# DR_EIB-128_MillMax.net
KiCad netlist of a schematic drawn in EAGLE
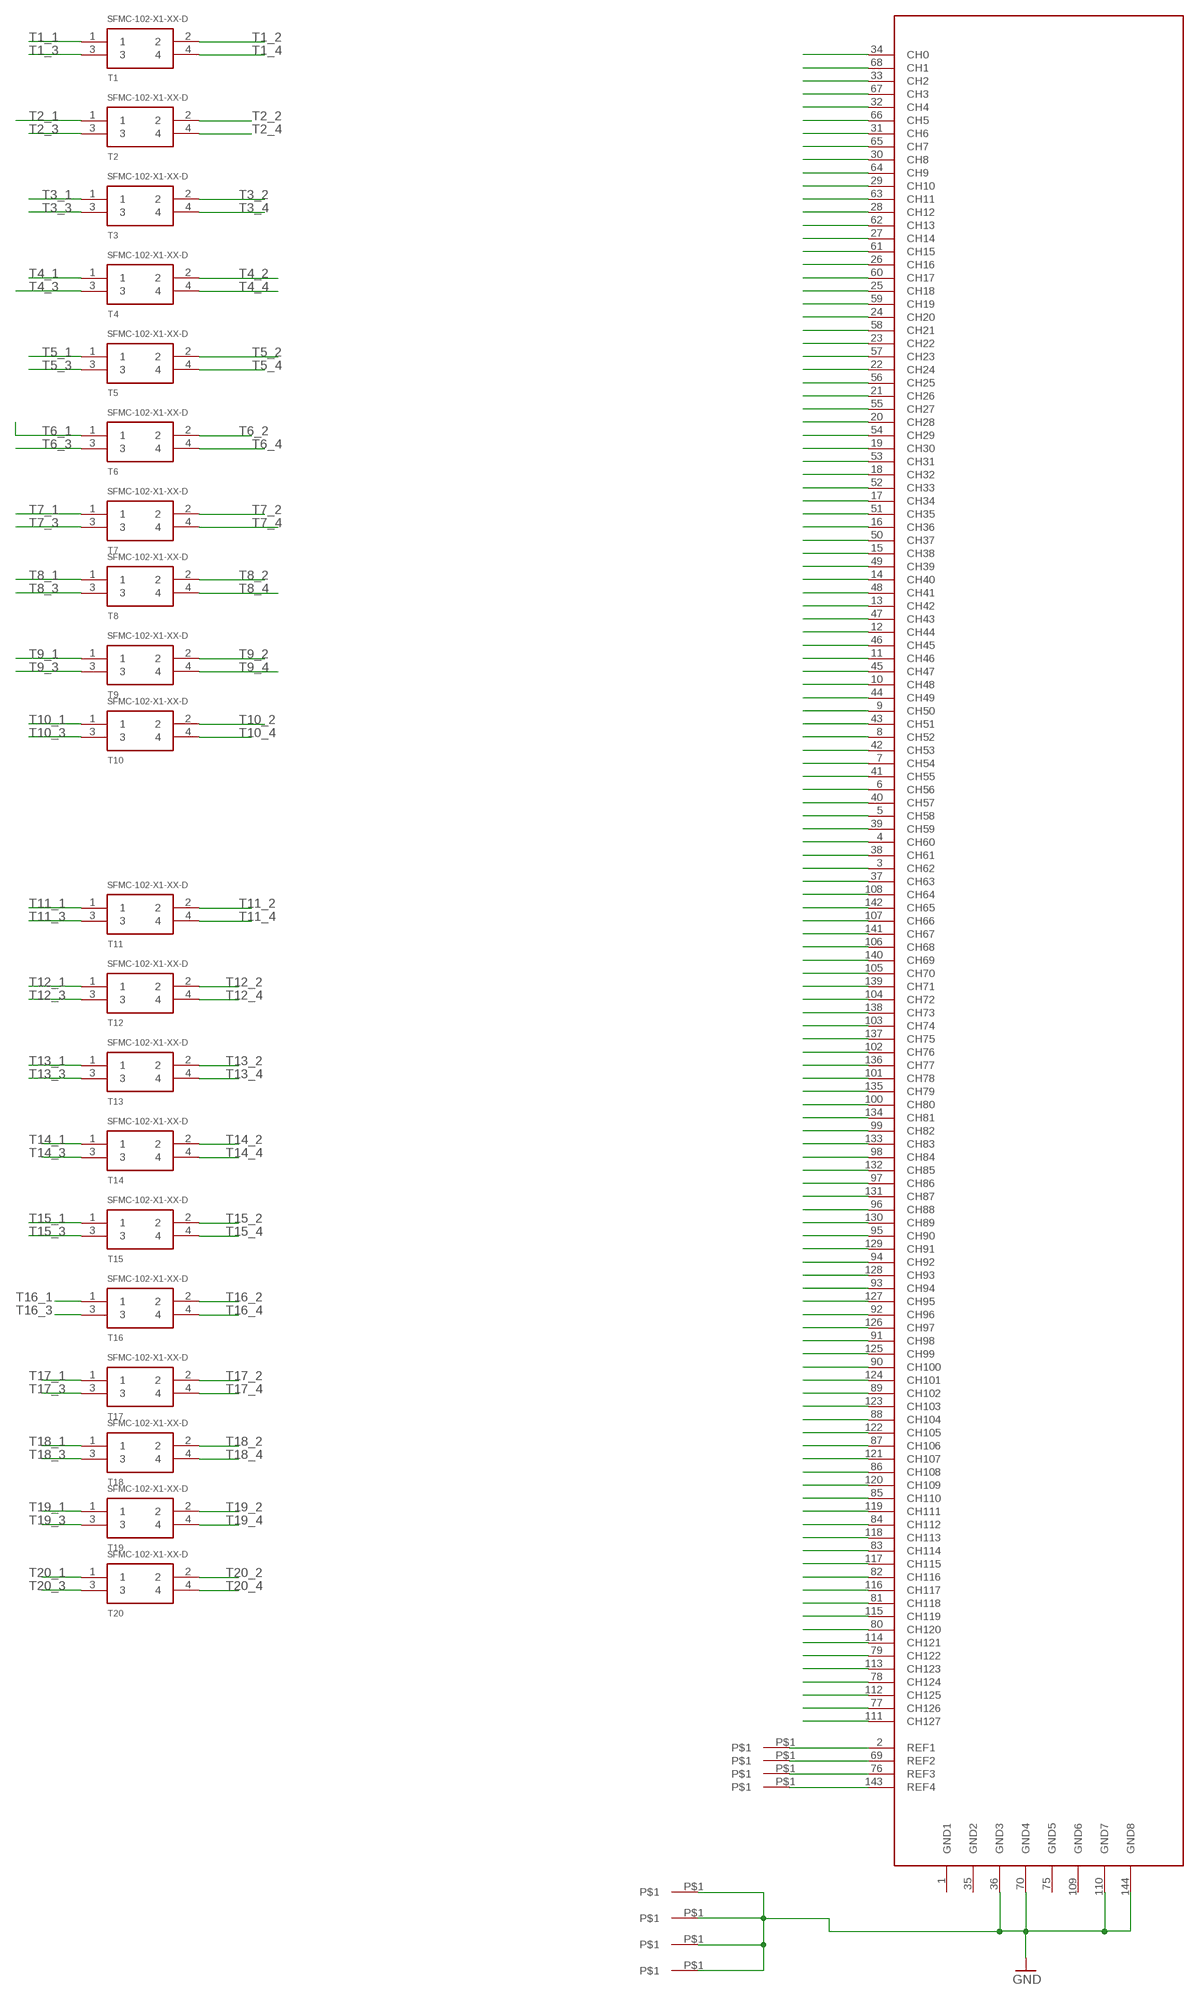
[diagram p0: schematic, sheet 1]

(export (version "E")
  (design (tool "Eeschema 10.0.6"))
  (components
    (comp (ref "T1")
      (value "SFMC-102-X1-XX-D")
      (footprint "eagle-import:SFMC-102-X1-XX-D")
      (libsource (lib "eagle-import") (part "SFMC-102-X1-XX-D"))
    )
    (comp (ref "T2")
      (value "SFMC-102-X1-XX-D")
      (footprint "eagle-import:SFMC-102-X1-XX-D")
      (libsource (lib "eagle-import") (part "SFMC-102-X1-XX-D"))
    )
    (comp (ref "T3")
      (value "SFMC-102-X1-XX-D")
      (footprint "eagle-import:SFMC-102-X1-XX-D")
      (libsource (lib "eagle-import") (part "SFMC-102-X1-XX-D"))
    )
    (comp (ref "T4")
      (value "SFMC-102-X1-XX-D")
      (footprint "eagle-import:SFMC-102-X1-XX-D")
      (libsource (lib "eagle-import") (part "SFMC-102-X1-XX-D"))
    )
    (comp (ref "T5")
      (value "SFMC-102-X1-XX-D")
      (footprint "eagle-import:SFMC-102-X1-XX-D")
      (libsource (lib "eagle-import") (part "SFMC-102-X1-XX-D"))
    )
    (comp (ref "T6")
      (value "SFMC-102-X1-XX-D")
      (footprint "eagle-import:SFMC-102-X1-XX-D")
      (libsource (lib "eagle-import") (part "SFMC-102-X1-XX-D"))
    )
    (comp (ref "T7")
      (value "SFMC-102-X1-XX-D")
      (footprint "eagle-import:SFMC-102-X1-XX-D")
      (libsource (lib "eagle-import") (part "SFMC-102-X1-XX-D"))
    )
    (comp (ref "T8")
      (value "SFMC-102-X1-XX-D")
      (footprint "eagle-import:SFMC-102-X1-XX-D")
      (libsource (lib "eagle-import") (part "SFMC-102-X1-XX-D"))
    )
    (comp (ref "T9")
      (value "SFMC-102-X1-XX-D")
      (footprint "eagle-import:SFMC-102-X1-XX-D")
      (libsource (lib "eagle-import") (part "SFMC-102-X1-XX-D"))
    )
    (comp (ref "T10")
      (value "SFMC-102-X1-XX-D")
      (footprint "eagle-import:SFMC-102-X1-XX-D")
      (libsource (lib "eagle-import") (part "SFMC-102-X1-XX-D"))
    )
    (comp (ref "T11")
      (value "SFMC-102-X1-XX-D")
      (footprint "eagle-import:SFMC-102-X1-XX-D")
      (libsource (lib "eagle-import") (part "SFMC-102-X1-XX-D"))
    )
    (comp (ref "T12")
      (value "SFMC-102-X1-XX-D")
      (footprint "eagle-import:SFMC-102-X1-XX-D")
      (libsource (lib "eagle-import") (part "SFMC-102-X1-XX-D"))
    )
    (comp (ref "T13")
      (value "SFMC-102-X1-XX-D")
      (footprint "eagle-import:SFMC-102-X1-XX-D")
      (libsource (lib "eagle-import") (part "SFMC-102-X1-XX-D"))
    )
    (comp (ref "T14")
      (value "SFMC-102-X1-XX-D")
      (footprint "eagle-import:SFMC-102-X1-XX-D")
      (libsource (lib "eagle-import") (part "SFMC-102-X1-XX-D"))
    )
    (comp (ref "T15")
      (value "SFMC-102-X1-XX-D")
      (footprint "eagle-import:SFMC-102-X1-XX-D")
      (libsource (lib "eagle-import") (part "SFMC-102-X1-XX-D"))
    )
    (comp (ref "T16")
      (value "SFMC-102-X1-XX-D")
      (footprint "eagle-import:SFMC-102-X1-XX-D")
      (libsource (lib "eagle-import") (part "SFMC-102-X1-XX-D"))
    )
    (comp (ref "T17")
      (value "SFMC-102-X1-XX-D")
      (footprint "eagle-import:SFMC-102-X1-XX-D")
      (libsource (lib "eagle-import") (part "SFMC-102-X1-XX-D"))
    )
    (comp (ref "T18")
      (value "SFMC-102-X1-XX-D")
      (footprint "eagle-import:SFMC-102-X1-XX-D")
      (libsource (lib "eagle-import") (part "SFMC-102-X1-XX-D"))
    )
    (comp (ref "T19")
      (value "SFMC-102-X1-XX-D")
      (footprint "eagle-import:SFMC-102-X1-XX-D")
      (libsource (lib "eagle-import") (part "SFMC-102-X1-XX-D"))
    )
    (comp (ref "T20")
      (value "SFMC-102-X1-XX-D")
      (footprint "eagle-import:SFMC-102-X1-XX-D")
      (libsource (lib "eagle-import") (part "SFMC-102-X1-XX-D"))
    )
    (comp (ref "U$1")
      (value "TARRAYSHUTTLEHOLE")
      (footprint "eagle-import:TARRAYSHUTTLEHOLE")
      (libsource (lib "eagle-import") (part "TARRAYSHUTTLEHOLE"))
    )
    (comp (ref "U$2")
      (value "TARRAYSHUTTLEHOLE")
      (footprint "eagle-import:TARRAYSHUTTLEHOLE")
      (libsource (lib "eagle-import") (part "TARRAYSHUTTLEHOLE"))
    )
    (comp (ref "U$3")
      (value "128CH-MODULE")
      (footprint "eagle-import:128CH-MODULE")
      (libsource (lib "eagle-import") (part "128CH-MODULE"))
    )
    (comp (ref "U$4")
      (value "TARRAYSHUTTLEHOLE")
      (footprint "eagle-import:TARRAYSHUTTLEHOLE")
      (libsource (lib "eagle-import") (part "TARRAYSHUTTLEHOLE"))
    )
    (comp (ref "U$5")
      (value "TARRAYSHUTTLEHOLE")
      (footprint "eagle-import:TARRAYSHUTTLEHOLE")
      (libsource (lib "eagle-import") (part "TARRAYSHUTTLEHOLE"))
    )
    (comp (ref "U$6")
      (value "TARRAYSHUTTLEHOLE")
      (footprint "eagle-import:TARRAYSHUTTLEHOLE")
      (libsource (lib "eagle-import") (part "TARRAYSHUTTLEHOLE"))
    )
    (comp (ref "U$7")
      (value "TARRAYSHUTTLEHOLE")
      (footprint "eagle-import:TARRAYSHUTTLEHOLE")
      (libsource (lib "eagle-import") (part "TARRAYSHUTTLEHOLE"))
    )
    (comp (ref "U$8")
      (value "TARRAYSHUTTLEHOLE")
      (footprint "eagle-import:TARRAYSHUTTLEHOLE")
      (libsource (lib "eagle-import") (part "TARRAYSHUTTLEHOLE"))
    )
    (comp (ref "U$9")
      (value "TARRAYSHUTTLEHOLE")
      (footprint "eagle-import:TARRAYSHUTTLEHOLE")
      (libsource (lib "eagle-import") (part "TARRAYSHUTTLEHOLE"))
    )
  )
  (nets
    (net (code "1") (name "/GND1") (class "Default")
      (node (ref "U$3") (pin "1") (pinfunction "GND1_1") (pintype "power_in"))
    )
    (net (code "2") (name "/GND2") (class "Default")
      (node (ref "U$3") (pin "35") (pinfunction "GND2_35") (pintype "power_in"))
    )
    (net (code "3") (name "/GND5") (class "Default")
      (node (ref "U$3") (pin "75") (pinfunction "GND5_75") (pintype "power_in"))
    )
    (net (code "4") (name "/GND6") (class "Default")
      (node (ref "U$3") (pin "109") (pinfunction "GND6_109") (pintype "power_in"))
    )
    (net (code "5") (name "/T1_1") (class "Default")
      (node (ref "T1") (pin "1") (pinfunction "1_1") (pintype "bidirectional"))
      (node (ref "U$3") (pin "37") (pinfunction "CH63_37") (pintype "input"))
    )
    (net (code "6") (name "/T1_2") (class "Default")
      (node (ref "T1") (pin "2") (pinfunction "2_2") (pintype "bidirectional"))
      (node (ref "U$3") (pin "38") (pinfunction "CH61_38") (pintype "input"))
    )
    (net (code "7") (name "/T1_3") (class "Default")
      (node (ref "T1") (pin "3") (pinfunction "3_3") (pintype "bidirectional"))
      (node (ref "U$3") (pin "39") (pinfunction "CH59_39") (pintype "input"))
    )
    (net (code "8") (name "/T1_4") (class "Default")
      (node (ref "T1") (pin "4") (pinfunction "4_4") (pintype "bidirectional"))
      (node (ref "U$3") (pin "40") (pinfunction "CH57_40") (pintype "input"))
    )
    (net (code "9") (name "/T2_1") (class "Default")
      (node (ref "T2") (pin "1") (pinfunction "1_1") (pintype "bidirectional"))
      (node (ref "U$3") (pin "6") (pinfunction "CH56_6") (pintype "input"))
    )
    (net (code "10") (name "/T2_2") (class "Default")
      (node (ref "T2") (pin "2") (pinfunction "2_2") (pintype "bidirectional"))
      (node (ref "U$3") (pin "5") (pinfunction "CH58_5") (pintype "input"))
    )
    (net (code "11") (name "/T2_3") (class "Default")
      (node (ref "T2") (pin "3") (pinfunction "3_3") (pintype "bidirectional"))
      (node (ref "U$3") (pin "4") (pinfunction "CH60_4") (pintype "input"))
    )
    (net (code "12") (name "/T2_4") (class "Default")
      (node (ref "T2") (pin "4") (pinfunction "4_4") (pintype "bidirectional"))
      (node (ref "U$3") (pin "3") (pinfunction "CH62_3") (pintype "input"))
    )
    (net (code "13") (name "/T3_1") (class "Default")
      (node (ref "T3") (pin "1") (pinfunction "1_1") (pintype "bidirectional"))
      (node (ref "U$3") (pin "7") (pinfunction "CH54_7") (pintype "input"))
    )
    (net (code "14") (name "/T3_2") (class "Default")
      (node (ref "T3") (pin "2") (pinfunction "2_2") (pintype "bidirectional"))
      (node (ref "U$3") (pin "8") (pinfunction "CH52_8") (pintype "input"))
    )
    (net (code "15") (name "/T3_3") (class "Default")
      (node (ref "T3") (pin "3") (pinfunction "3_3") (pintype "bidirectional"))
      (node (ref "U$3") (pin "9") (pinfunction "CH50_9") (pintype "input"))
    )
    (net (code "16") (name "/T3_4") (class "Default")
      (node (ref "T3") (pin "4") (pinfunction "4_4") (pintype "bidirectional"))
      (node (ref "U$3") (pin "10") (pinfunction "CH48_10") (pintype "input"))
    )
    (net (code "17") (name "/T4_1") (class "Default")
      (node (ref "T4") (pin "1") (pinfunction "1_1") (pintype "bidirectional"))
      (node (ref "U$3") (pin "11") (pinfunction "CH46_11") (pintype "input"))
    )
    (net (code "18") (name "/T4_2") (class "Default")
      (node (ref "T4") (pin "2") (pinfunction "2_2") (pintype "bidirectional"))
      (node (ref "U$3") (pin "12") (pinfunction "CH44_12") (pintype "input"))
    )
    (net (code "19") (name "/T4_3") (class "Default")
      (node (ref "T4") (pin "3") (pinfunction "3_3") (pintype "bidirectional"))
      (node (ref "U$3") (pin "13") (pinfunction "CH42_13") (pintype "input"))
    )
    (net (code "20") (name "/T4_4") (class "Default")
      (node (ref "T4") (pin "4") (pinfunction "4_4") (pintype "bidirectional"))
      (node (ref "U$3") (pin "14") (pinfunction "CH40_14") (pintype "input"))
    )
    (net (code "21") (name "/T5_1") (class "Default")
      (node (ref "T5") (pin "1") (pinfunction "1_1") (pintype "bidirectional"))
      (node (ref "U$3") (pin "15") (pinfunction "CH38_15") (pintype "input"))
    )
    (net (code "22") (name "/T5_2") (class "Default")
      (node (ref "T5") (pin "2") (pinfunction "2_2") (pintype "bidirectional"))
      (node (ref "U$3") (pin "16") (pinfunction "CH36_16") (pintype "input"))
    )
    (net (code "23") (name "/T5_3") (class "Default")
      (node (ref "T5") (pin "3") (pinfunction "3_3") (pintype "bidirectional"))
      (node (ref "U$3") (pin "17") (pinfunction "CH34_17") (pintype "input"))
    )
    (net (code "24") (name "/T5_4") (class "Default")
      (node (ref "T5") (pin "4") (pinfunction "4_4") (pintype "bidirectional"))
      (node (ref "U$3") (pin "18") (pinfunction "CH32_18") (pintype "input"))
    )
    (net (code "25") (name "/T6_1") (class "Default")
      (node (ref "T6") (pin "1") (pinfunction "1_1") (pintype "bidirectional"))
      (node (ref "U$3") (pin "93") (pinfunction "CH94_93") (pintype "input"))
    )
    (net (code "26") (name "/T6_2") (class "Default")
      (node (ref "T6") (pin "2") (pinfunction "2_2") (pintype "bidirectional"))
      (node (ref "U$3") (pin "94") (pinfunction "CH92_94") (pintype "input"))
    )
    (net (code "27") (name "/T6_3") (class "Default")
      (node (ref "T6") (pin "3") (pinfunction "3_3") (pintype "bidirectional"))
      (node (ref "U$3") (pin "95") (pinfunction "CH90_95") (pintype "input"))
    )
    (net (code "28") (name "/T6_4") (class "Default")
      (node (ref "T6") (pin "4") (pinfunction "4_4") (pintype "bidirectional"))
      (node (ref "U$3") (pin "96") (pinfunction "CH88_96") (pintype "input"))
    )
    (net (code "29") (name "/T7_1") (class "Default")
      (node (ref "T7") (pin "1") (pinfunction "1_1") (pintype "bidirectional"))
      (node (ref "U$3") (pin "97") (pinfunction "CH86_97") (pintype "input"))
    )
    (net (code "30") (name "/T7_2") (class "Default")
      (node (ref "T7") (pin "2") (pinfunction "2_2") (pintype "bidirectional"))
      (node (ref "U$3") (pin "98") (pinfunction "CH84_98") (pintype "input"))
    )
    (net (code "31") (name "/T7_3") (class "Default")
      (node (ref "T7") (pin "3") (pinfunction "3_3") (pintype "bidirectional"))
      (node (ref "U$3") (pin "99") (pinfunction "CH82_99") (pintype "input"))
    )
    (net (code "32") (name "/T7_4") (class "Default")
      (node (ref "T7") (pin "4") (pinfunction "4_4") (pintype "bidirectional"))
      (node (ref "U$3") (pin "100") (pinfunction "CH80_100") (pintype "input"))
    )
    (net (code "33") (name "/T8_1") (class "Default")
      (node (ref "T8") (pin "1") (pinfunction "1_1") (pintype "bidirectional"))
      (node (ref "U$3") (pin "101") (pinfunction "CH78_101") (pintype "input"))
    )
    (net (code "34") (name "/T8_2") (class "Default")
      (node (ref "T8") (pin "2") (pinfunction "2_2") (pintype "bidirectional"))
      (node (ref "U$3") (pin "102") (pinfunction "CH76_102") (pintype "input"))
    )
    (net (code "35") (name "/T8_3") (class "Default")
      (node (ref "T8") (pin "3") (pinfunction "3_3") (pintype "bidirectional"))
      (node (ref "U$3") (pin "103") (pinfunction "CH74_103") (pintype "input"))
    )
    (net (code "36") (name "/T8_4") (class "Default")
      (node (ref "T8") (pin "4") (pinfunction "4_4") (pintype "bidirectional"))
      (node (ref "U$3") (pin "104") (pinfunction "CH72_104") (pintype "input"))
    )
    (net (code "37") (name "/T9_1") (class "Default")
      (node (ref "T9") (pin "1") (pinfunction "1_1") (pintype "bidirectional"))
      (node (ref "U$3") (pin "108") (pinfunction "CH64_108") (pintype "input"))
    )
    (net (code "38") (name "/T9_2") (class "Default")
      (node (ref "T9") (pin "2") (pinfunction "2_2") (pintype "bidirectional"))
      (node (ref "U$3") (pin "107") (pinfunction "CH66_107") (pintype "input"))
    )
    (net (code "39") (name "/T9_3") (class "Default")
      (node (ref "T9") (pin "3") (pinfunction "3_3") (pintype "bidirectional"))
      (node (ref "U$3") (pin "106") (pinfunction "CH68_106") (pintype "input"))
    )
    (net (code "40") (name "/T9_4") (class "Default")
      (node (ref "T9") (pin "4") (pinfunction "4_4") (pintype "bidirectional"))
      (node (ref "U$3") (pin "105") (pinfunction "CH70_105") (pintype "input"))
    )
    (net (code "41") (name "/T10_1") (class "Default")
      (node (ref "T10") (pin "1") (pinfunction "1_1") (pintype "bidirectional"))
      (node (ref "U$3") (pin "139") (pinfunction "CH71_139") (pintype "input"))
    )
    (net (code "42") (name "/T10_2") (class "Default")
      (node (ref "T10") (pin "2") (pinfunction "2_2") (pintype "bidirectional"))
      (node (ref "U$3") (pin "140") (pinfunction "CH69_140") (pintype "input"))
    )
    (net (code "43") (name "/T10_3") (class "Default")
      (node (ref "T10") (pin "3") (pinfunction "3_3") (pintype "bidirectional"))
      (node (ref "U$3") (pin "141") (pinfunction "CH67_141") (pintype "input"))
    )
    (net (code "44") (name "/T10_4") (class "Default")
      (node (ref "T10") (pin "4") (pinfunction "4_4") (pintype "bidirectional"))
      (node (ref "U$3") (pin "142") (pinfunction "CH65_142") (pintype "input"))
    )
    (net (code "45") (name "/T11_1") (class "Default")
      (node (ref "T11") (pin "1") (pinfunction "1_1") (pintype "bidirectional"))
      (node (ref "U$3") (pin "111") (pinfunction "CH127_111") (pintype "input"))
    )
    (net (code "46") (name "/T11_2") (class "Default")
      (node (ref "T11") (pin "2") (pinfunction "2_2") (pintype "bidirectional"))
      (node (ref "U$3") (pin "112") (pinfunction "CH125_112") (pintype "input"))
    )
    (net (code "47") (name "/T11_3") (class "Default")
      (node (ref "T11") (pin "3") (pinfunction "3_3") (pintype "bidirectional"))
      (node (ref "U$3") (pin "113") (pinfunction "CH123_113") (pintype "input"))
    )
    (net (code "48") (name "/T11_4") (class "Default")
      (node (ref "T11") (pin "4") (pinfunction "4_4") (pintype "bidirectional"))
      (node (ref "U$3") (pin "114") (pinfunction "CH121_114") (pintype "input"))
    )
    (net (code "49") (name "/T12_1") (class "Default")
      (node (ref "T12") (pin "1") (pinfunction "1_1") (pintype "bidirectional"))
      (node (ref "U$3") (pin "80") (pinfunction "CH120_80") (pintype "input"))
    )
    (net (code "50") (name "/T12_2") (class "Default")
      (node (ref "T12") (pin "2") (pinfunction "2_2") (pintype "bidirectional"))
      (node (ref "U$3") (pin "79") (pinfunction "CH122_79") (pintype "input"))
    )
    (net (code "51") (name "/T12_3") (class "Default")
      (node (ref "T12") (pin "3") (pinfunction "3_3") (pintype "bidirectional"))
      (node (ref "U$3") (pin "78") (pinfunction "CH124_78") (pintype "input"))
    )
    (net (code "52") (name "/T12_4") (class "Default")
      (node (ref "T12") (pin "4") (pinfunction "4_4") (pintype "bidirectional"))
      (node (ref "U$3") (pin "77") (pinfunction "CH126_77") (pintype "input"))
    )
    (net (code "53") (name "/T13_1") (class "Default")
      (node (ref "T13") (pin "1") (pinfunction "1_1") (pintype "bidirectional"))
      (node (ref "U$3") (pin "81") (pinfunction "CH118_81") (pintype "input"))
    )
    (net (code "54") (name "/T13_2") (class "Default")
      (node (ref "T13") (pin "2") (pinfunction "2_2") (pintype "bidirectional"))
      (node (ref "U$3") (pin "82") (pinfunction "CH116_82") (pintype "input"))
    )
    (net (code "55") (name "/T13_3") (class "Default")
      (node (ref "T13") (pin "3") (pinfunction "3_3") (pintype "bidirectional"))
      (node (ref "U$3") (pin "83") (pinfunction "CH114_83") (pintype "input"))
    )
    (net (code "56") (name "/T13_4") (class "Default")
      (node (ref "T13") (pin "4") (pinfunction "4_4") (pintype "bidirectional"))
      (node (ref "U$3") (pin "84") (pinfunction "CH112_84") (pintype "input"))
    )
    (net (code "57") (name "/T14_1") (class "Default")
      (node (ref "T14") (pin "1") (pinfunction "1_1") (pintype "bidirectional"))
      (node (ref "U$3") (pin "85") (pinfunction "CH110_85") (pintype "input"))
    )
    (net (code "58") (name "/T14_2") (class "Default")
      (node (ref "T14") (pin "2") (pinfunction "2_2") (pintype "bidirectional"))
      (node (ref "U$3") (pin "86") (pinfunction "CH108_86") (pintype "input"))
    )
    (net (code "59") (name "/T14_3") (class "Default")
      (node (ref "T14") (pin "3") (pinfunction "3_3") (pintype "bidirectional"))
      (node (ref "U$3") (pin "87") (pinfunction "CH106_87") (pintype "input"))
    )
    (net (code "60") (name "/T14_4") (class "Default")
      (node (ref "T14") (pin "4") (pinfunction "4_4") (pintype "bidirectional"))
      (node (ref "U$3") (pin "88") (pinfunction "CH104_88") (pintype "input"))
    )
    (net (code "61") (name "/T15_1") (class "Default")
      (node (ref "T15") (pin "1") (pinfunction "1_1") (pintype "bidirectional"))
      (node (ref "U$3") (pin "89") (pinfunction "CH102_89") (pintype "input"))
    )
    (net (code "62") (name "/T15_2") (class "Default")
      (node (ref "T15") (pin "2") (pinfunction "2_2") (pintype "bidirectional"))
      (node (ref "U$3") (pin "90") (pinfunction "CH100_90") (pintype "input"))
    )
    (net (code "63") (name "/T15_3") (class "Default")
      (node (ref "T15") (pin "3") (pinfunction "3_3") (pintype "bidirectional"))
      (node (ref "U$3") (pin "91") (pinfunction "CH98_91") (pintype "input"))
    )
    (net (code "64") (name "/T15_4") (class "Default")
      (node (ref "T15") (pin "4") (pinfunction "4_4") (pintype "bidirectional"))
      (node (ref "U$3") (pin "92") (pinfunction "CH96_92") (pintype "input"))
    )
    (net (code "65") (name "/T16_1") (class "Default")
      (node (ref "T16") (pin "1") (pinfunction "1_1") (pintype "bidirectional"))
      (node (ref "U$3") (pin "19") (pinfunction "CH30_19") (pintype "input"))
    )
    (net (code "66") (name "/T16_2") (class "Default")
      (node (ref "T16") (pin "2") (pinfunction "2_2") (pintype "bidirectional"))
      (node (ref "U$3") (pin "20") (pinfunction "CH28_20") (pintype "input"))
    )
    (net (code "67") (name "/T16_3") (class "Default")
      (node (ref "T16") (pin "3") (pinfunction "3_3") (pintype "bidirectional"))
      (node (ref "U$3") (pin "21") (pinfunction "CH26_21") (pintype "input"))
    )
    (net (code "68") (name "/T16_4") (class "Default")
      (node (ref "T16") (pin "4") (pinfunction "4_4") (pintype "bidirectional"))
      (node (ref "U$3") (pin "22") (pinfunction "CH24_22") (pintype "input"))
    )
    (net (code "69") (name "/T17_1") (class "Default")
      (node (ref "T17") (pin "1") (pinfunction "1_1") (pintype "bidirectional"))
      (node (ref "U$3") (pin "23") (pinfunction "CH22_23") (pintype "input"))
    )
    (net (code "70") (name "/T17_2") (class "Default")
      (node (ref "T17") (pin "2") (pinfunction "2_2") (pintype "bidirectional"))
      (node (ref "U$3") (pin "24") (pinfunction "CH20_24") (pintype "input"))
    )
    (net (code "71") (name "/T17_3") (class "Default")
      (node (ref "T17") (pin "3") (pinfunction "3_3") (pintype "bidirectional"))
      (node (ref "U$3") (pin "25") (pinfunction "CH18_25") (pintype "input"))
    )
    (net (code "72") (name "/T17_4") (class "Default")
      (node (ref "T17") (pin "4") (pinfunction "4_4") (pintype "bidirectional"))
      (node (ref "U$3") (pin "26") (pinfunction "CH16_26") (pintype "input"))
    )
    (net (code "73") (name "/T18_1") (class "Default")
      (node (ref "T18") (pin "1") (pinfunction "1_1") (pintype "bidirectional"))
      (node (ref "U$3") (pin "27") (pinfunction "CH14_27") (pintype "input"))
    )
    (net (code "74") (name "/T18_2") (class "Default")
      (node (ref "T18") (pin "2") (pinfunction "2_2") (pintype "bidirectional"))
      (node (ref "U$3") (pin "28") (pinfunction "CH12_28") (pintype "input"))
    )
    (net (code "75") (name "/T18_3") (class "Default")
      (node (ref "T18") (pin "3") (pinfunction "3_3") (pintype "bidirectional"))
      (node (ref "U$3") (pin "29") (pinfunction "CH10_29") (pintype "input"))
    )
    (net (code "76") (name "/T18_4") (class "Default")
      (node (ref "T18") (pin "4") (pinfunction "4_4") (pintype "bidirectional"))
      (node (ref "U$3") (pin "30") (pinfunction "CH8_30") (pintype "input"))
    )
    (net (code "77") (name "/T19_1") (class "Default")
      (node (ref "T19") (pin "1") (pinfunction "1_1") (pintype "bidirectional"))
      (node (ref "U$3") (pin "34") (pinfunction "CH0_34") (pintype "input"))
    )
    (net (code "78") (name "/T19_2") (class "Default")
      (node (ref "T19") (pin "2") (pinfunction "2_2") (pintype "bidirectional"))
      (node (ref "U$3") (pin "33") (pinfunction "CH2_33") (pintype "input"))
    )
    (net (code "79") (name "/T19_3") (class "Default")
      (node (ref "T19") (pin "3") (pinfunction "3_3") (pintype "bidirectional"))
      (node (ref "U$3") (pin "32") (pinfunction "CH4_32") (pintype "input"))
    )
    (net (code "80") (name "/T19_4") (class "Default")
      (node (ref "T19") (pin "4") (pinfunction "4_4") (pintype "bidirectional"))
      (node (ref "U$3") (pin "31") (pinfunction "CH6_31") (pintype "input"))
    )
    (net (code "81") (name "/T20_1") (class "Default")
      (node (ref "T20") (pin "1") (pinfunction "1_1") (pintype "bidirectional"))
      (node (ref "U$3") (pin "65") (pinfunction "CH7_65") (pintype "input"))
    )
    (net (code "82") (name "/T20_2") (class "Default")
      (node (ref "T20") (pin "2") (pinfunction "2_2") (pintype "bidirectional"))
      (node (ref "U$3") (pin "66") (pinfunction "CH5_66") (pintype "input"))
    )
    (net (code "83") (name "/T20_3") (class "Default")
      (node (ref "T20") (pin "3") (pinfunction "3_3") (pintype "bidirectional"))
      (node (ref "U$3") (pin "67") (pinfunction "CH3_67") (pintype "input"))
    )
    (net (code "84") (name "/T20_4") (class "Default")
      (node (ref "T20") (pin "4") (pinfunction "4_4") (pintype "bidirectional"))
      (node (ref "U$3") (pin "68") (pinfunction "CH1_68") (pintype "input"))
    )
    (net (code "85") (name "GND") (class "Default")
      (node (ref "U$1") (pin "P$1") (pinfunction "P$1_P$1") (pintype "bidirectional"))
      (node (ref "U$2") (pin "P$1") (pinfunction "P$1_P$1") (pintype "bidirectional"))
      (node (ref "U$3") (pin "110") (pinfunction "GND7_110") (pintype "power_in"))
      (node (ref "U$3") (pin "144") (pinfunction "GND8_144") (pintype "power_in"))
      (node (ref "U$3") (pin "36") (pinfunction "GND3_36") (pintype "power_in"))
      (node (ref "U$3") (pin "70") (pinfunction "GND4_70") (pintype "power_in"))
      (node (ref "U$4") (pin "P$1") (pinfunction "P$1_P$1") (pintype "bidirectional"))
      (node (ref "U$5") (pin "P$1") (pinfunction "P$1_P$1") (pintype "bidirectional"))
    )
    (net (code "86") (name "Net-(U$3-REF1)") (class "Default")
      (node (ref "U$3") (pin "2") (pinfunction "REF1_2") (pintype "input"))
      (node (ref "U$6") (pin "P$1") (pinfunction "P$1_P$1") (pintype "bidirectional"))
    )
    (net (code "87") (name "Net-(U$3-REF2)") (class "Default")
      (node (ref "U$3") (pin "69") (pinfunction "REF2_69") (pintype "input"))
      (node (ref "U$7") (pin "P$1") (pinfunction "P$1_P$1") (pintype "bidirectional"))
    )
    (net (code "88") (name "Net-(U$3-REF3)") (class "Default")
      (node (ref "U$3") (pin "76") (pinfunction "REF3_76") (pintype "input"))
      (node (ref "U$8") (pin "P$1") (pinfunction "P$1_P$1") (pintype "bidirectional"))
    )
    (net (code "89") (name "Net-(U$3-REF4)") (class "Default")
      (node (ref "U$3") (pin "143") (pinfunction "REF4_143") (pintype "input"))
      (node (ref "U$9") (pin "P$1") (pinfunction "P$1_P$1") (pintype "bidirectional"))
    )
    (net (code "90") (name "unconnected-(U$3-CH9-Pad64)") (class "Default")
      (node (ref "U$3") (pin "64") (pinfunction "CH9_64") (pintype "input"))
    )
    (net (code "91") (name "unconnected-(U$3-CH11-Pad63)") (class "Default")
      (node (ref "U$3") (pin "63") (pinfunction "CH11_63") (pintype "input"))
    )
    (net (code "92") (name "unconnected-(U$3-CH13-Pad62)") (class "Default")
      (node (ref "U$3") (pin "62") (pinfunction "CH13_62") (pintype "input"))
    )
    (net (code "93") (name "unconnected-(U$3-CH15-Pad61)") (class "Default")
      (node (ref "U$3") (pin "61") (pinfunction "CH15_61") (pintype "input"))
    )
    (net (code "94") (name "unconnected-(U$3-CH17-Pad60)") (class "Default")
      (node (ref "U$3") (pin "60") (pinfunction "CH17_60") (pintype "input"))
    )
    (net (code "95") (name "unconnected-(U$3-CH19-Pad59)") (class "Default")
      (node (ref "U$3") (pin "59") (pinfunction "CH19_59") (pintype "input"))
    )
    (net (code "96") (name "unconnected-(U$3-CH21-Pad58)") (class "Default")
      (node (ref "U$3") (pin "58") (pinfunction "CH21_58") (pintype "input"))
    )
    (net (code "97") (name "unconnected-(U$3-CH23-Pad57)") (class "Default")
      (node (ref "U$3") (pin "57") (pinfunction "CH23_57") (pintype "input"))
    )
    (net (code "98") (name "unconnected-(U$3-CH25-Pad56)") (class "Default")
      (node (ref "U$3") (pin "56") (pinfunction "CH25_56") (pintype "input"))
    )
    (net (code "99") (name "unconnected-(U$3-CH27-Pad55)") (class "Default")
      (node (ref "U$3") (pin "55") (pinfunction "CH27_55") (pintype "input"))
    )
    (net (code "100") (name "unconnected-(U$3-CH29-Pad54)") (class "Default")
      (node (ref "U$3") (pin "54") (pinfunction "CH29_54") (pintype "input"))
    )
    (net (code "101") (name "unconnected-(U$3-CH31-Pad53)") (class "Default")
      (node (ref "U$3") (pin "53") (pinfunction "CH31_53") (pintype "input"))
    )
    (net (code "102") (name "unconnected-(U$3-CH33-Pad52)") (class "Default")
      (node (ref "U$3") (pin "52") (pinfunction "CH33_52") (pintype "input"))
    )
    (net (code "103") (name "unconnected-(U$3-CH35-Pad51)") (class "Default")
      (node (ref "U$3") (pin "51") (pinfunction "CH35_51") (pintype "input"))
    )
    (net (code "104") (name "unconnected-(U$3-CH37-Pad50)") (class "Default")
      (node (ref "U$3") (pin "50") (pinfunction "CH37_50") (pintype "input"))
    )
    (net (code "105") (name "unconnected-(U$3-CH39-Pad49)") (class "Default")
      (node (ref "U$3") (pin "49") (pinfunction "CH39_49") (pintype "input"))
    )
    (net (code "106") (name "unconnected-(U$3-CH41-Pad48)") (class "Default")
      (node (ref "U$3") (pin "48") (pinfunction "CH41_48") (pintype "input"))
    )
    (net (code "107") (name "unconnected-(U$3-CH43-Pad47)") (class "Default")
      (node (ref "U$3") (pin "47") (pinfunction "CH43_47") (pintype "input"))
    )
    (net (code "108") (name "unconnected-(U$3-CH45-Pad46)") (class "Default")
      (node (ref "U$3") (pin "46") (pinfunction "CH45_46") (pintype "input"))
    )
    (net (code "109") (name "unconnected-(U$3-CH47-Pad45)") (class "Default")
      (node (ref "U$3") (pin "45") (pinfunction "CH47_45") (pintype "input"))
    )
    (net (code "110") (name "unconnected-(U$3-CH49-Pad44)") (class "Default")
      (node (ref "U$3") (pin "44") (pinfunction "CH49_44") (pintype "input"))
    )
    (net (code "111") (name "unconnected-(U$3-CH51-Pad43)") (class "Default")
      (node (ref "U$3") (pin "43") (pinfunction "CH51_43") (pintype "input"))
    )
    (net (code "112") (name "unconnected-(U$3-CH53-Pad42)") (class "Default")
      (node (ref "U$3") (pin "42") (pinfunction "CH53_42") (pintype "input"))
    )
    (net (code "113") (name "unconnected-(U$3-CH55-Pad41)") (class "Default")
      (node (ref "U$3") (pin "41") (pinfunction "CH55_41") (pintype "input"))
    )
    (net (code "114") (name "unconnected-(U$3-CH73-Pad138)") (class "Default")
      (node (ref "U$3") (pin "138") (pinfunction "CH73_138") (pintype "input"))
    )
    (net (code "115") (name "unconnected-(U$3-CH75-Pad137)") (class "Default")
      (node (ref "U$3") (pin "137") (pinfunction "CH75_137") (pintype "input"))
    )
    (net (code "116") (name "unconnected-(U$3-CH77-Pad136)") (class "Default")
      (node (ref "U$3") (pin "136") (pinfunction "CH77_136") (pintype "input"))
    )
    (net (code "117") (name "unconnected-(U$3-CH79-Pad135)") (class "Default")
      (node (ref "U$3") (pin "135") (pinfunction "CH79_135") (pintype "input"))
    )
    (net (code "118") (name "unconnected-(U$3-CH81-Pad134)") (class "Default")
      (node (ref "U$3") (pin "134") (pinfunction "CH81_134") (pintype "input"))
    )
    (net (code "119") (name "unconnected-(U$3-CH83-Pad133)") (class "Default")
      (node (ref "U$3") (pin "133") (pinfunction "CH83_133") (pintype "input"))
    )
    (net (code "120") (name "unconnected-(U$3-CH85-Pad132)") (class "Default")
      (node (ref "U$3") (pin "132") (pinfunction "CH85_132") (pintype "input"))
    )
    (net (code "121") (name "unconnected-(U$3-CH87-Pad131)") (class "Default")
      (node (ref "U$3") (pin "131") (pinfunction "CH87_131") (pintype "input"))
    )
    (net (code "122") (name "unconnected-(U$3-CH89-Pad130)") (class "Default")
      (node (ref "U$3") (pin "130") (pinfunction "CH89_130") (pintype "input"))
    )
    (net (code "123") (name "unconnected-(U$3-CH91-Pad129)") (class "Default")
      (node (ref "U$3") (pin "129") (pinfunction "CH91_129") (pintype "input"))
    )
    (net (code "124") (name "unconnected-(U$3-CH93-Pad128)") (class "Default")
      (node (ref "U$3") (pin "128") (pinfunction "CH93_128") (pintype "input"))
    )
    (net (code "125") (name "unconnected-(U$3-CH95-Pad127)") (class "Default")
      (node (ref "U$3") (pin "127") (pinfunction "CH95_127") (pintype "input"))
    )
    (net (code "126") (name "unconnected-(U$3-CH97-Pad126)") (class "Default")
      (node (ref "U$3") (pin "126") (pinfunction "CH97_126") (pintype "input"))
    )
    (net (code "127") (name "unconnected-(U$3-CH99-Pad125)") (class "Default")
      (node (ref "U$3") (pin "125") (pinfunction "CH99_125") (pintype "input"))
    )
    (net (code "128") (name "unconnected-(U$3-CH101-Pad124)") (class "Default")
      (node (ref "U$3") (pin "124") (pinfunction "CH101_124") (pintype "input"))
    )
    (net (code "129") (name "unconnected-(U$3-CH103-Pad123)") (class "Default")
      (node (ref "U$3") (pin "123") (pinfunction "CH103_123") (pintype "input"))
    )
    (net (code "130") (name "unconnected-(U$3-CH105-Pad122)") (class "Default")
      (node (ref "U$3") (pin "122") (pinfunction "CH105_122") (pintype "input"))
    )
    (net (code "131") (name "unconnected-(U$3-CH107-Pad121)") (class "Default")
      (node (ref "U$3") (pin "121") (pinfunction "CH107_121") (pintype "input"))
    )
    (net (code "132") (name "unconnected-(U$3-CH109-Pad120)") (class "Default")
      (node (ref "U$3") (pin "120") (pinfunction "CH109_120") (pintype "input"))
    )
    (net (code "133") (name "unconnected-(U$3-CH111-Pad119)") (class "Default")
      (node (ref "U$3") (pin "119") (pinfunction "CH111_119") (pintype "input"))
    )
    (net (code "134") (name "unconnected-(U$3-CH113-Pad118)") (class "Default")
      (node (ref "U$3") (pin "118") (pinfunction "CH113_118") (pintype "input"))
    )
    (net (code "135") (name "unconnected-(U$3-CH115-Pad117)") (class "Default")
      (node (ref "U$3") (pin "117") (pinfunction "CH115_117") (pintype "input"))
    )
    (net (code "136") (name "unconnected-(U$3-CH117-Pad116)") (class "Default")
      (node (ref "U$3") (pin "116") (pinfunction "CH117_116") (pintype "input"))
    )
    (net (code "137") (name "unconnected-(U$3-CH119-Pad115)") (class "Default")
      (node (ref "U$3") (pin "115") (pinfunction "CH119_115") (pintype "input"))
    )
  )
)
